# u.net
KiCad netlist of a schematic drawn in EasyEDA
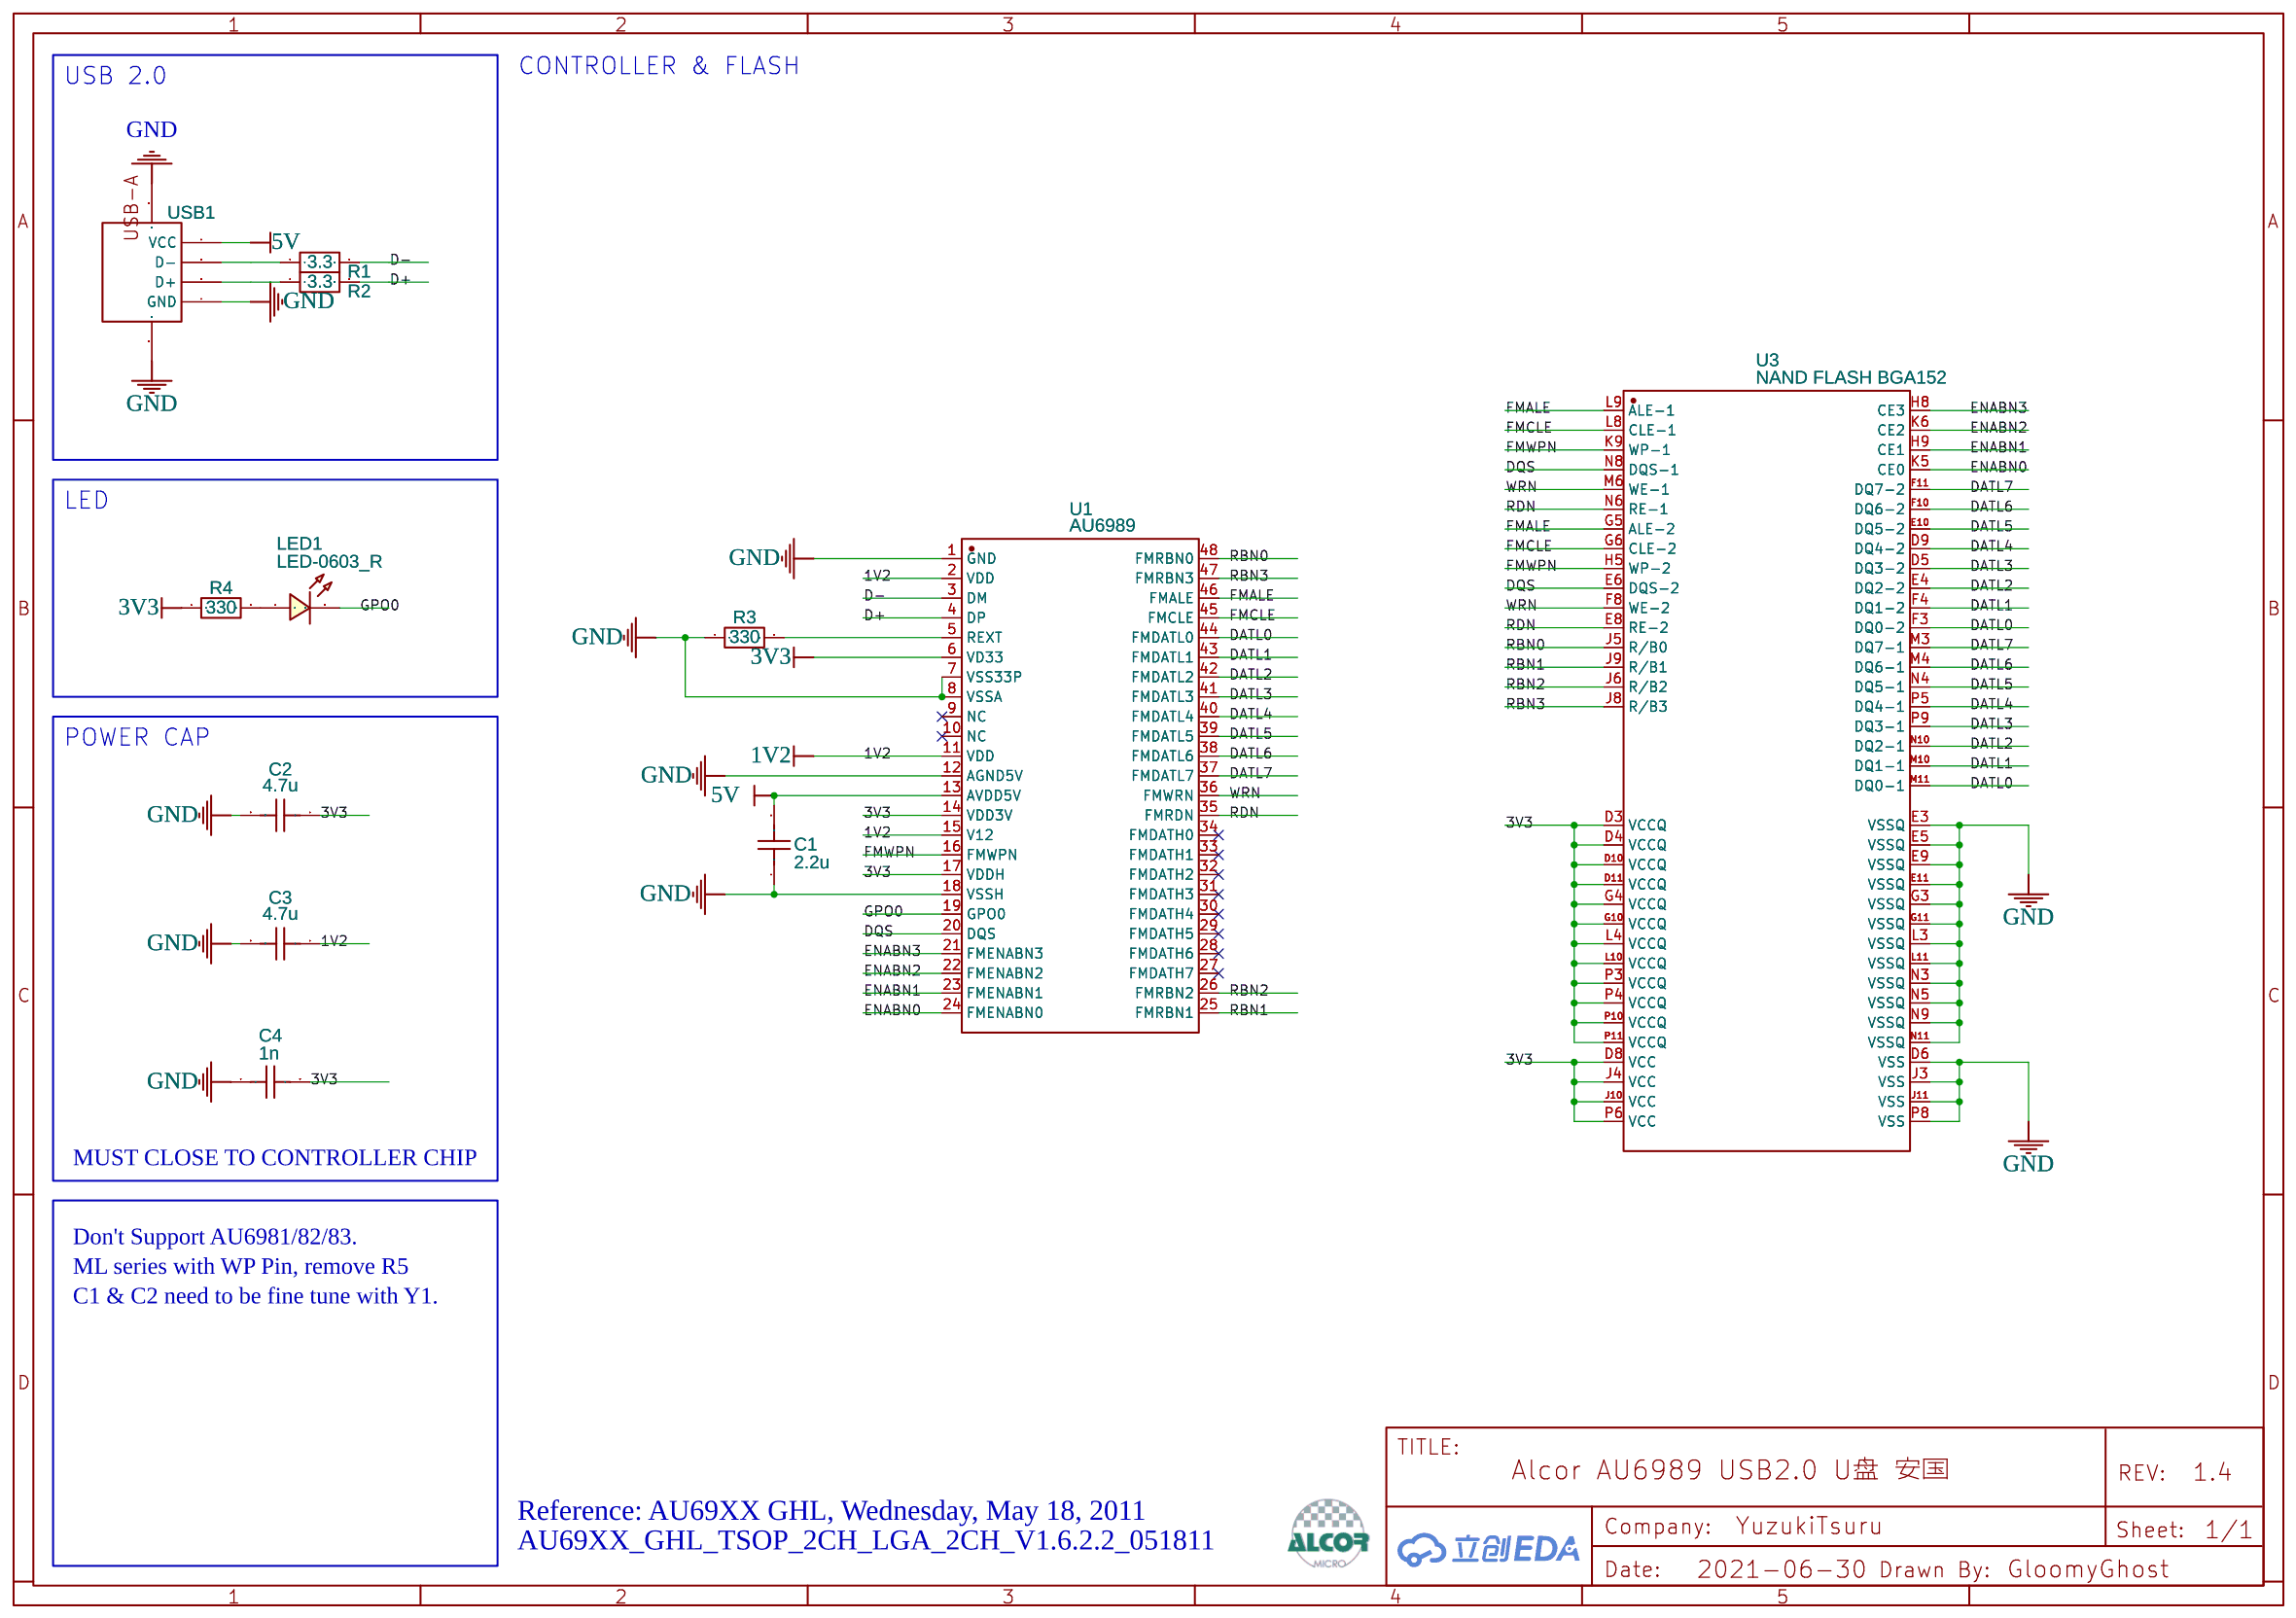
[diagram p0: schematic sheet]

(export (version "E")
  (design (tool "Eeschema 10.0.6"))
  (components
    (comp (ref "C1") (value "2.2u") (libsource (lib "") (part "C_0603_US")))
    (comp (ref "C2") (value "4.7u") (libsource (lib "") (part "C_0603_US_1")))
    (comp (ref "C3") (value "4.7u") (libsource (lib "") (part "C_0603_US_1")))
    (comp (ref "C4") (value "1n") (libsource (lib "") (part "C_0603_US_2")))
    (comp (ref "LED1")
      (value "LED-0603_R")
      (fields
        (field (name "BOM_Manufacturer Part") "19-217/R6C-AL1M2VY/3T")
        (field (name "BOM_Supplier Part") "C72044")
      )
      (libsource (lib "") (part "LED-0603_R"))
    )
    (comp (ref "R1") (value "3.3") (libsource (lib "") (part "R_0603_EU")))
    (comp (ref "R2") (value "3.3") (libsource (lib "") (part "R_0603_EU")))
    (comp (ref "R3") (value "330") (libsource (lib "") (part "R_0603_EU")))
    (comp (ref "R4") (value "330") (libsource (lib "") (part "R_0603_EU")))
    (comp (ref "U1") (value "AU6989") (libsource (lib "") (part "AU6989")))
    (comp (ref "U3") (value "NAND FLASH BGA152") (libsource (lib "") (part "NAND FLASH BGA152")))
    (comp (ref "USB1")
      (value "USB-A-A/M Stick plate bent legs VinylPBT With a column")
      (fields
        (field (name "BOM_Manufacturer Part") "A/M Stick plate bent legs VinylPBT With a column")
        (field (name "BOM_Supplier Part") "C46394")
      )
      (libsource (lib "") (part "USB-A-A/M Stick plate bent legs VinylPBT With a column"))
    )
  )
  (nets
    (net (code "1") (name "/D+") (class "Default")
      (node (ref "R2") (pin "2") (pinfunction "2_2") (pintype "unspecified"))
      (node (ref "U1") (pin "4") (pinfunction "DP_4") (pintype "unspecified"))
    )
    (net (code "2") (name "/D-") (class "Default")
      (node (ref "R1") (pin "2") (pinfunction "2_2") (pintype "unspecified"))
      (node (ref "U1") (pin "3") (pinfunction "DM_3") (pintype "unspecified"))
    )
    (net (code "3") (name "/DATL0") (class "Default")
      (node (ref "U1") (pin "44") (pinfunction "FMDATL0_44") (pintype "unspecified"))
      (node (ref "U3") (pin "F3") (pinfunction "DQ0-2_F3") (pintype "unspecified"))
      (node (ref "U3") (pin "M11") (pinfunction "DQ0-1_M11") (pintype "unspecified"))
    )
    (net (code "4") (name "/DATL1") (class "Default")
      (node (ref "U1") (pin "43") (pinfunction "FMDATL1_43") (pintype "unspecified"))
      (node (ref "U3") (pin "F4") (pinfunction "DQ1-2_F4") (pintype "unspecified"))
      (node (ref "U3") (pin "M10") (pinfunction "DQ1-1_M10") (pintype "unspecified"))
    )
    (net (code "5") (name "/DATL2") (class "Default")
      (node (ref "U1") (pin "42") (pinfunction "FMDATL2_42") (pintype "unspecified"))
      (node (ref "U3") (pin "E4") (pinfunction "DQ2-2_E4") (pintype "unspecified"))
      (node (ref "U3") (pin "N10") (pinfunction "DQ2-1_N10") (pintype "unspecified"))
    )
    (net (code "6") (name "/DATL3") (class "Default")
      (node (ref "U1") (pin "41") (pinfunction "FMDATL3_41") (pintype "unspecified"))
      (node (ref "U3") (pin "D5") (pinfunction "DQ3-2_D5") (pintype "unspecified"))
      (node (ref "U3") (pin "P9") (pinfunction "DQ3-1_P9") (pintype "unspecified"))
    )
    (net (code "7") (name "/DATL4") (class "Default")
      (node (ref "U1") (pin "40") (pinfunction "FMDATL4_40") (pintype "unspecified"))
      (node (ref "U3") (pin "D9") (pinfunction "DQ4-2_D9") (pintype "unspecified"))
      (node (ref "U3") (pin "P5") (pinfunction "DQ4-1_P5") (pintype "unspecified"))
    )
    (net (code "8") (name "/DATL5") (class "Default")
      (node (ref "U1") (pin "39") (pinfunction "FMDATL5_39") (pintype "unspecified"))
      (node (ref "U3") (pin "E10") (pinfunction "DQ5-2_E10") (pintype "unspecified"))
      (node (ref "U3") (pin "N4") (pinfunction "DQ5-1_N4") (pintype "unspecified"))
    )
    (net (code "9") (name "/DATL6") (class "Default")
      (node (ref "U1") (pin "38") (pinfunction "FMDATL6_38") (pintype "unspecified"))
      (node (ref "U3") (pin "F10") (pinfunction "DQ6-2_F10") (pintype "unspecified"))
      (node (ref "U3") (pin "M4") (pinfunction "DQ6-1_M4") (pintype "unspecified"))
    )
    (net (code "10") (name "/DATL7") (class "Default")
      (node (ref "U1") (pin "37") (pinfunction "FMDATL7_37") (pintype "unspecified"))
      (node (ref "U3") (pin "F11") (pinfunction "DQ7-2_F11") (pintype "unspecified"))
      (node (ref "U3") (pin "M3") (pinfunction "DQ7-1_M3") (pintype "unspecified"))
    )
    (net (code "11") (name "/DQS") (class "Default")
      (node (ref "U1") (pin "20") (pinfunction "DQS_20") (pintype "unspecified"))
      (node (ref "U3") (pin "E6") (pinfunction "DQS-2_E6") (pintype "unspecified"))
      (node (ref "U3") (pin "N8") (pinfunction "DQS-1_N8") (pintype "unspecified"))
    )
    (net (code "12") (name "/ENABN0") (class "Default")
      (node (ref "U1") (pin "24") (pinfunction "FMENABN0_24") (pintype "unspecified"))
      (node (ref "U3") (pin "K5") (pinfunction "CE0_K5") (pintype "unspecified"))
    )
    (net (code "13") (name "/ENABN1") (class "Default")
      (node (ref "U1") (pin "23") (pinfunction "FMENABN1_23") (pintype "unspecified"))
      (node (ref "U3") (pin "H9") (pinfunction "CE1_H9") (pintype "unspecified"))
    )
    (net (code "14") (name "/ENABN2") (class "Default")
      (node (ref "U1") (pin "22") (pinfunction "FMENABN2_22") (pintype "unspecified"))
      (node (ref "U3") (pin "K6") (pinfunction "CE2_K6") (pintype "unspecified"))
    )
    (net (code "15") (name "/ENABN3") (class "Default")
      (node (ref "U1") (pin "21") (pinfunction "FMENABN3_21") (pintype "unspecified"))
      (node (ref "U3") (pin "H8") (pinfunction "CE3_H8") (pintype "unspecified"))
    )
    (net (code "16") (name "/FMALE") (class "Default")
      (node (ref "U1") (pin "46") (pinfunction "FMALE_46") (pintype "unspecified"))
      (node (ref "U3") (pin "G5") (pinfunction "ALE-2_G5") (pintype "unspecified"))
      (node (ref "U3") (pin "L9") (pinfunction "ALE-1_L9") (pintype "unspecified"))
    )
    (net (code "17") (name "/FMCLE") (class "Default")
      (node (ref "U1") (pin "45") (pinfunction "FMCLE_45") (pintype "unspecified"))
      (node (ref "U3") (pin "G6") (pinfunction "CLE-2_G6") (pintype "unspecified"))
      (node (ref "U3") (pin "L8") (pinfunction "CLE-1_L8") (pintype "unspecified"))
    )
    (net (code "18") (name "/FMWPN") (class "Default")
      (node (ref "U1") (pin "16") (pinfunction "FMWPN_16") (pintype "unspecified"))
      (node (ref "U3") (pin "H5") (pinfunction "WP-2_H5") (pintype "unspecified"))
      (node (ref "U3") (pin "K9") (pinfunction "WP-1_K9") (pintype "unspecified"))
    )
    (net (code "19") (name "/GPO0") (class "Default")
      (node (ref "LED1") (pin "2") (pinfunction "2_2") (pintype "unspecified"))
      (node (ref "U1") (pin "19") (pinfunction "GPO0_19") (pintype "unspecified"))
    )
    (net (code "20") (name "/RBN0") (class "Default")
      (node (ref "U1") (pin "48") (pinfunction "FMRBN0_48") (pintype "unspecified"))
      (node (ref "U3") (pin "J5") (pinfunction "R/B0_J5") (pintype "unspecified"))
    )
    (net (code "21") (name "/RBN1") (class "Default")
      (node (ref "U1") (pin "25") (pinfunction "FMRBN1_25") (pintype "unspecified"))
      (node (ref "U3") (pin "J9") (pinfunction "R/B1_J9") (pintype "unspecified"))
    )
    (net (code "22") (name "/RBN2") (class "Default")
      (node (ref "U1") (pin "26") (pinfunction "FMRBN2_26") (pintype "unspecified"))
      (node (ref "U3") (pin "J6") (pinfunction "R/B2_J6") (pintype "unspecified"))
    )
    (net (code "23") (name "/RBN3") (class "Default")
      (node (ref "U1") (pin "47") (pinfunction "FMRBN3_47") (pintype "unspecified"))
      (node (ref "U3") (pin "J8") (pinfunction "R/B3_J8") (pintype "unspecified"))
    )
    (net (code "24") (name "/RDN") (class "Default")
      (node (ref "U1") (pin "35") (pinfunction "FMRDN_35") (pintype "unspecified"))
      (node (ref "U3") (pin "E8") (pinfunction "RE-2_E8") (pintype "unspecified"))
      (node (ref "U3") (pin "N6") (pinfunction "RE-1_N6") (pintype "unspecified"))
    )
    (net (code "25") (name "/WRN") (class "Default")
      (node (ref "U1") (pin "36") (pinfunction "FMWRN_36") (pintype "unspecified"))
      (node (ref "U3") (pin "F8") (pinfunction "WE-2_F8") (pintype "unspecified"))
      (node (ref "U3") (pin "M6") (pinfunction "WE-1_M6") (pintype "unspecified"))
    )
    (net (code "26") (name "1V2") (class "Default")
      (node (ref "C3") (pin "1") (pinfunction "1_1") (pintype "unspecified"))
      (node (ref "U1") (pin "11") (pinfunction "VDD_11") (pintype "unspecified"))
      (node (ref "U1") (pin "15") (pinfunction "V12_15") (pintype "unspecified"))
      (node (ref "U1") (pin "2") (pinfunction "VDD_2") (pintype "unspecified"))
    )
    (net (code "27") (name "3V3") (class "Default")
      (node (ref "C2") (pin "1") (pinfunction "1_1") (pintype "unspecified"))
      (node (ref "C4") (pin "2") (pinfunction "2_2") (pintype "unspecified"))
      (node (ref "R4") (pin "1") (pinfunction "1_1") (pintype "unspecified"))
      (node (ref "U1") (pin "14") (pinfunction "VDD3V_14") (pintype "unspecified"))
      (node (ref "U1") (pin "17") (pinfunction "VDDH_17") (pintype "unspecified"))
      (node (ref "U1") (pin "6") (pinfunction "VD33_6") (pintype "unspecified"))
      (node (ref "U3") (pin "D10") (pinfunction "VCCQ_D10") (pintype "unspecified"))
      (node (ref "U3") (pin "D11") (pinfunction "VCCQ_D11") (pintype "unspecified"))
      (node (ref "U3") (pin "D3") (pinfunction "VCCQ_D3") (pintype "unspecified"))
      (node (ref "U3") (pin "D4") (pinfunction "VCCQ_D4") (pintype "unspecified"))
      (node (ref "U3") (pin "D8") (pinfunction "VCC_D8") (pintype "unspecified"))
      (node (ref "U3") (pin "G10") (pinfunction "VCCQ_G10") (pintype "unspecified"))
      (node (ref "U3") (pin "G4") (pinfunction "VCCQ_G4") (pintype "unspecified"))
      (node (ref "U3") (pin "J10") (pinfunction "VCC_J10") (pintype "unspecified"))
      (node (ref "U3") (pin "J4") (pinfunction "VCC_J4") (pintype "unspecified"))
      (node (ref "U3") (pin "L10") (pinfunction "VCCQ_L10") (pintype "unspecified"))
      (node (ref "U3") (pin "L4") (pinfunction "VCCQ_L4") (pintype "unspecified"))
      (node (ref "U3") (pin "P10") (pinfunction "VCCQ_P10") (pintype "unspecified"))
      (node (ref "U3") (pin "P11") (pinfunction "VCCQ_P11") (pintype "unspecified"))
      (node (ref "U3") (pin "P3") (pinfunction "VCCQ_P3") (pintype "unspecified"))
      (node (ref "U3") (pin "P4") (pinfunction "VCCQ_P4") (pintype "unspecified"))
      (node (ref "U3") (pin "P6") (pinfunction "VCC_P6") (pintype "unspecified"))
    )
    (net (code "28") (name "5V") (class "Default")
      (node (ref "C1") (pin "2") (pinfunction "2_2") (pintype "unspecified"))
      (node (ref "U1") (pin "13") (pinfunction "AVDD5V_13") (pintype "unspecified"))
      (node (ref "USB1") (pin "1") (pinfunction "VCC_1") (pintype "input"))
    )
    (net (code "29") (name "GND") (class "Default")
      (node (ref "C1") (pin "1") (pinfunction "1_1") (pintype "unspecified"))
      (node (ref "C2") (pin "2") (pinfunction "2_2") (pintype "unspecified"))
      (node (ref "C3") (pin "2") (pinfunction "2_2") (pintype "unspecified"))
      (node (ref "C4") (pin "1") (pinfunction "1_1") (pintype "unspecified"))
      (node (ref "R3") (pin "1") (pinfunction "1_1") (pintype "unspecified"))
      (node (ref "U1") (pin "1") (pinfunction "GND_1") (pintype "unspecified"))
      (node (ref "U1") (pin "12") (pinfunction "AGND5V_12") (pintype "unspecified"))
      (node (ref "U1") (pin "18") (pinfunction "VSSH_18") (pintype "unspecified"))
      (node (ref "U1") (pin "7") (pinfunction "VSS33P_7") (pintype "unspecified"))
      (node (ref "U1") (pin "8") (pinfunction "VSSA_8") (pintype "unspecified"))
      (node (ref "U3") (pin "D6") (pinfunction "VSS_D6") (pintype "unspecified"))
      (node (ref "U3") (pin "E11") (pinfunction "VSSQ_E11") (pintype "unspecified"))
      (node (ref "U3") (pin "E3") (pinfunction "VSSQ_E3") (pintype "unspecified"))
      (node (ref "U3") (pin "E5") (pinfunction "VSSQ_E5") (pintype "unspecified"))
      (node (ref "U3") (pin "E9") (pinfunction "VSSQ_E9") (pintype "unspecified"))
      (node (ref "U3") (pin "G11") (pinfunction "VSSQ_G11") (pintype "unspecified"))
      (node (ref "U3") (pin "G3") (pinfunction "VSSQ_G3") (pintype "unspecified"))
      (node (ref "U3") (pin "J11") (pinfunction "VSS_J11") (pintype "unspecified"))
      (node (ref "U3") (pin "J3") (pinfunction "VSS_J3") (pintype "unspecified"))
      (node (ref "U3") (pin "L11") (pinfunction "VSSQ_L11") (pintype "unspecified"))
      (node (ref "U3") (pin "L3") (pinfunction "VSSQ_L3") (pintype "unspecified"))
      (node (ref "U3") (pin "N11") (pinfunction "VSSQ_N11") (pintype "unspecified"))
      (node (ref "U3") (pin "N3") (pinfunction "VSSQ_N3") (pintype "unspecified"))
      (node (ref "U3") (pin "N5") (pinfunction "VSSQ_N5") (pintype "unspecified"))
      (node (ref "U3") (pin "N9") (pinfunction "VSSQ_N9") (pintype "unspecified"))
      (node (ref "U3") (pin "P8") (pinfunction "VSS_P8") (pintype "unspecified"))
      (node (ref "USB1") (pin "4") (pinfunction "GND_4") (pintype "input"))
      (node (ref "USB1") (pin "5") (pinfunction "5_5") (pintype "unspecified"))
      (node (ref "USB1") (pin "6") (pinfunction "6_6") (pintype "unspecified"))
    )
    (net (code "30") (name "Net-(LED1-Pad1)") (class "Default")
      (node (ref "LED1") (pin "1") (pinfunction "1_1") (pintype "unspecified"))
      (node (ref "R4") (pin "2") (pinfunction "2_2") (pintype "unspecified"))
    )
    (net (code "31") (name "Net-(U1-REXT)") (class "Default")
      (node (ref "R3") (pin "2") (pinfunction "2_2") (pintype "unspecified"))
      (node (ref "U1") (pin "5") (pinfunction "REXT_5") (pintype "unspecified"))
    )
    (net (code "32") (name "Net-(USB1-D+)") (class "Default")
      (node (ref "R2") (pin "1") (pinfunction "1_1") (pintype "unspecified"))
      (node (ref "USB1") (pin "3") (pinfunction "D+_3") (pintype "input"))
    )
    (net (code "33") (name "Net-(USB1-D-)") (class "Default")
      (node (ref "R1") (pin "1") (pinfunction "1_1") (pintype "unspecified"))
      (node (ref "USB1") (pin "2") (pinfunction "D-_2") (pintype "input"))
    )
    (net (code "34") (name "unconnected-(U1-FMDATH0-Pad34)") (class "Default")
      (node (ref "U1") (pin "34") (pinfunction "FMDATH0_34") (pintype "unspecified+no_connect"))
    )
    (net (code "35") (name "unconnected-(U1-FMDATH1-Pad33)") (class "Default")
      (node (ref "U1") (pin "33") (pinfunction "FMDATH1_33") (pintype "unspecified+no_connect"))
    )
    (net (code "36") (name "unconnected-(U1-FMDATH2-Pad32)") (class "Default")
      (node (ref "U1") (pin "32") (pinfunction "FMDATH2_32") (pintype "unspecified+no_connect"))
    )
    (net (code "37") (name "unconnected-(U1-FMDATH3-Pad31)") (class "Default")
      (node (ref "U1") (pin "31") (pinfunction "FMDATH3_31") (pintype "unspecified+no_connect"))
    )
    (net (code "38") (name "unconnected-(U1-FMDATH4-Pad30)") (class "Default")
      (node (ref "U1") (pin "30") (pinfunction "FMDATH4_30") (pintype "unspecified+no_connect"))
    )
    (net (code "39") (name "unconnected-(U1-FMDATH5-Pad29)") (class "Default")
      (node (ref "U1") (pin "29") (pinfunction "FMDATH5_29") (pintype "unspecified+no_connect"))
    )
    (net (code "40") (name "unconnected-(U1-FMDATH6-Pad28)") (class "Default")
      (node (ref "U1") (pin "28") (pinfunction "FMDATH6_28") (pintype "unspecified+no_connect"))
    )
    (net (code "41") (name "unconnected-(U1-FMDATH7-Pad27)") (class "Default")
      (node (ref "U1") (pin "27") (pinfunction "FMDATH7_27") (pintype "unspecified+no_connect"))
    )
    (net (code "42") (name "unconnected-(U1-NC-Pad9)") (class "Default")
      (node (ref "U1") (pin "9") (pinfunction "NC_9") (pintype "unspecified+no_connect"))
    )
    (net (code "43") (name "unconnected-(U1-NC-Pad10)") (class "Default")
      (node (ref "U1") (pin "10") (pinfunction "NC_10") (pintype "unspecified+no_connect"))
    )
  )
)
